# HX711_1.net
KiCad netlist of a schematic drawn in Altium Designer
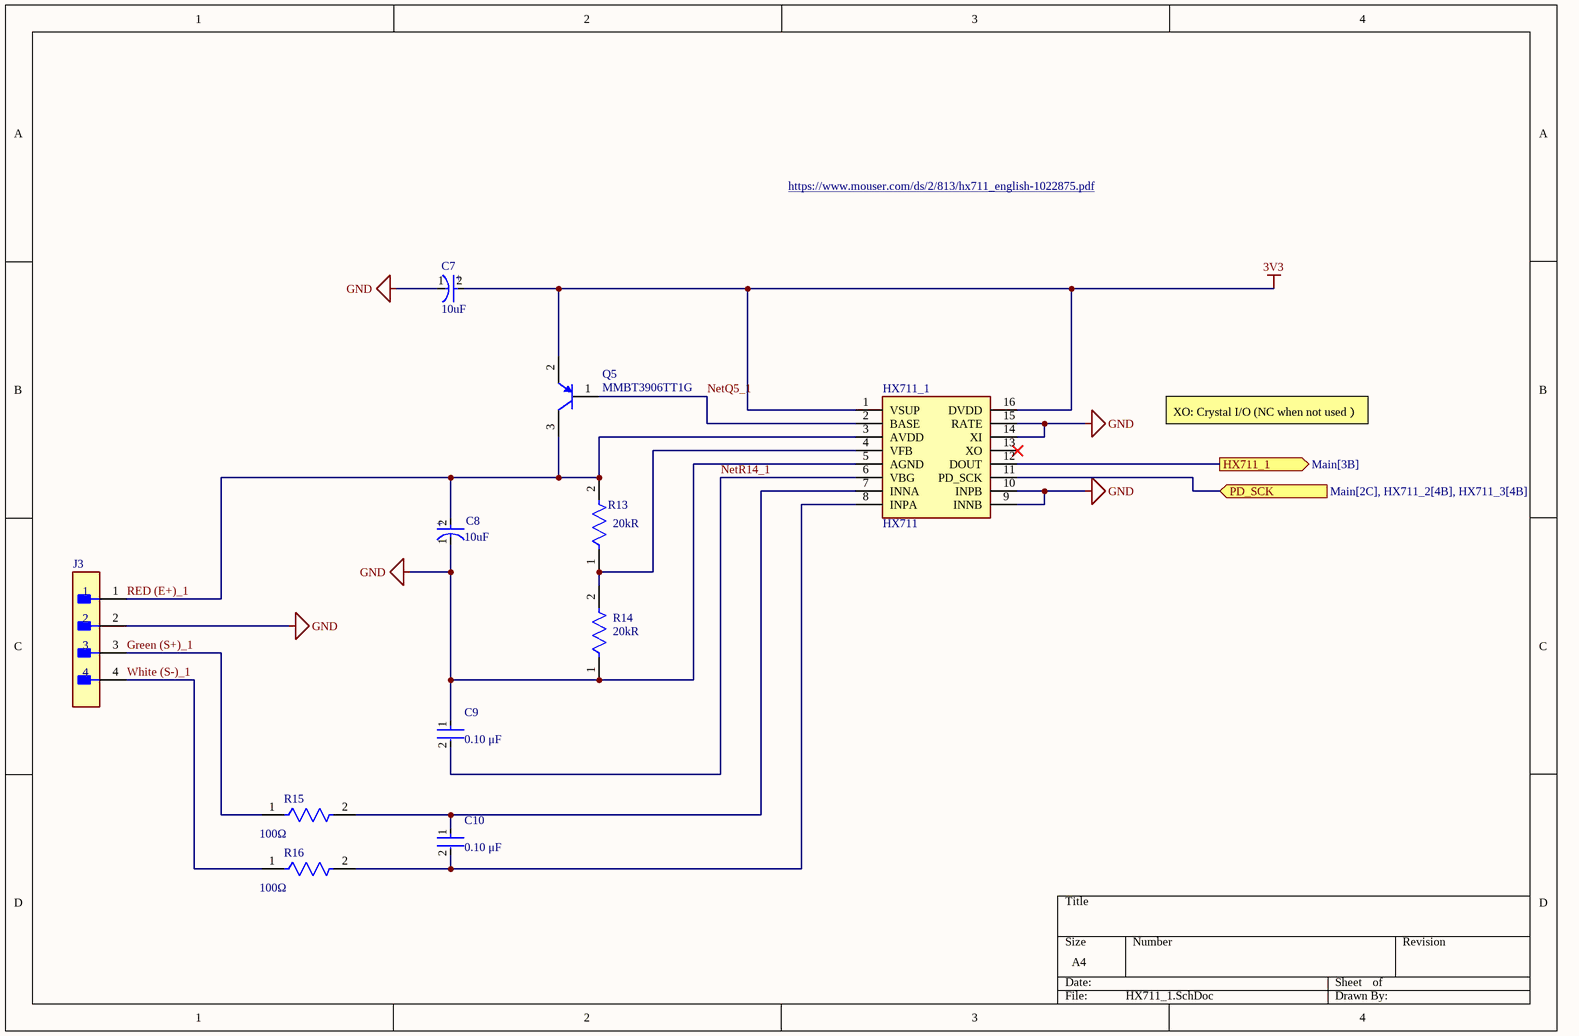
[diagram p0: HX711_1.SchDoc]

(export (version "E")
  (design (tool "Eeschema 10.0.6"))
  (components
    (comp (ref "C7")
      (value "EDK106M035A9BAA")
      (footprint "FP-EDK9B-MFG")
      (description "CAP ALUM 10UF 20% 35V SMD")
      (fields
        (field (name "CAPACITANCE") "10uF")
        (field (name "MANUFACTURER") "Kemet")
        (field (name "OCTOPART") "https://octopart.com/edk106m035a9baa-kemet-26722193")
      )
      (libsource (lib "Altium Content Vault") (part "cf48714ba7e38822c1575c7ec0b6d1f"))
    )
    (comp (ref "C8")
      (value "EDK106M035A9BAA")
      (footprint "FP-EDK9B-MFG")
      (description "CAP ALUM 10UF 20% 35V SMD")
      (fields
        (field (name "CAPACITANCE") "10uF")
        (field (name "MANUFACTURER") "Kemet")
        (field (name "OCTOPART") "https://octopart.com/edk106m035a9baa-kemet-26722193")
      )
      (libsource (lib "Altium Content Vault") (part "cf48714ba7e38822c1575c7ec0b6d1f"))
    )
    (comp (ref "C9")
      (value "0.10 μF")
      (footprint "FP-C0603C-CF-MFG")
      (description "CAP CER 0.1UF 25V X7R 0603")
      (fields
        (field (name "OCTOPART") "https://octopart.com/c0603c104k3rac7411-kemet-9138804")
        (field (name "MANUFACTURER") "KEMET")
      )
      (libsource (lib "Altium Content Vault") (part "b4654b650e69147ec39a6b967a45e02"))
    )
    (comp (ref "C10")
      (value "0.10 μF")
      (footprint "FP-C0603C-CF-MFG")
      (description "CAP CER 0.1UF 25V X7R 0603")
      (fields
        (field (name "OCTOPART") "https://octopart.com/c0603c104k3rac7411-kemet-9138804")
        (field (name "MANUFACTURER") "KEMET")
      )
      (libsource (lib "Altium Content Vault") (part "b4654b650e69147ec39a6b967a45e02"))
    )
    (comp (ref "HX711_1")
      (value "HX711")
      (footprint "SamacSys:SOIC127P600X160-16N")
      (description "Integrated Circuit")
      (libsource (lib "*") (part "HX711"))
    )
    (comp (ref "J3")
      (value "TSW-104-23-T-S")
      (footprint "FP-TSW-104-23-T-S-MFG")
      (description "CONN HEADER VERT 4POS 2.54MM")
      (libsource (lib "Altium Content Vault") (part "f33e0d423099bbb9e64512431cdbdf7"))
    )
    (comp (ref "Q5")
      (value "MMBT3906TT1G")
      (footprint "ONSC-SC-75-3-463-01_V")
      (description "General Purpose Transistor, PNP Silicon, 3-Pin SC-75, Pb-Free, Tape and Reel")
      (fields (field (name "MANUFACTURER") "On Semiconductor"))
      (libsource (lib "Altium Content Vault") (part "ONSC-PNP-B1E2C3-3"))
    )
    (comp (ref "R13")
      (value "CRCW060320K0FKEAHP")
      (footprint "FP-CRCW0603-HPe3-MFG")
      (description "RES Thick Film, 20kΩ, 1%, 0.33W, 100ppm/°C, 0603")
      (fields (field (name "RESISTANCE") "20kR") (field (name "TOLERANCE") "1%"))
      (libsource (lib "Altium Content Vault") (part "1029c3af85768c4190bb7ad29bc67b5"))
    )
    (comp (ref "R14")
      (value "CRCW060320K0FKEAHP")
      (footprint "FP-CRCW0603-HPe3-MFG")
      (description "RES Thick Film, 20kΩ, 1%, 0.33W, 100ppm/°C, 0603")
      (fields (field (name "RESISTANCE") "20kR") (field (name "TOLERANCE") "1%"))
      (libsource (lib "Altium Content Vault") (part "1029c3af85768c4190bb7ad29bc67b5"))
    )
    (comp (ref "R15")
      (value "100Ω")
      (footprint "FP-RT0603-MFG")
      (description "RES SMD 100 OHM 1% 1/10W 0603")
      (fields
        (field (name "MANUFACTURER PART NUMBER") "RT0603FRE07100RL")
        (field (name "MANUFACTURER") "Yageo")
      )
      (libsource (lib "Altium Content Vault") (part "1029c3af85768c4190bb7ad29bc67b5"))
    )
    (comp (ref "R16")
      (value "100Ω")
      (footprint "FP-RT0603-MFG")
      (description "RES SMD 100 OHM 1% 1/10W 0603")
      (fields
        (field (name "MANUFACTURER PART NUMBER") "RT0603FRE07100RL")
        (field (name "MANUFACTURER") "Yageo")
      )
      (libsource (lib "Altium Content Vault") (part "1029c3af85768c4190bb7ad29bc67b5"))
    )
  )
  (nets
    (net (code "1") (name "/Green (S+)_1") (class "Default")
      (node (ref "J3") (pin "3") (pinfunction "3_3") (pintype "passive"))
      (node (ref "R15") (pin "1") (pinfunction "1_1") (pintype "passive"))
    )
    (net (code "2") (name "/HX711_1") (class "Default")
      (node (ref "HX711_1") (pin "12") (pinfunction "DOUT_12") (pintype "passive"))
    )
    (net (code "3") (name "/NetQ5_1") (class "Default")
      (node (ref "HX711_1") (pin "2") (pinfunction "BASE_2") (pintype "passive"))
      (node (ref "Q5") (pin "1") (pinfunction "B_1") (pintype "passive"))
    )
    (net (code "4") (name "/NetR14_1") (class "Default")
      (node (ref "C9") (pin "2") (pinfunction "2_2") (pintype "passive"))
      (node (ref "HX711_1") (pin "6") (pinfunction "VBG_6") (pintype "passive"))
    )
    (net (code "5") (name "/PD_SCK") (class "Default")
      (node (ref "HX711_1") (pin "11") (pinfunction "PD_SCK_11") (pintype "passive"))
    )
    (net (code "6") (name "/RED (E+)_1") (class "Default")
      (node (ref "C8") (pin "2") (pinfunction "A_2") (pintype "passive"))
      (node (ref "HX711_1") (pin "3") (pinfunction "AVDD_3") (pintype "passive"))
      (node (ref "J3") (pin "1") (pinfunction "1_1") (pintype "passive"))
      (node (ref "Q5") (pin "3") (pinfunction "C_3") (pintype "passive"))
      (node (ref "R13") (pin "2") (pinfunction "2_2") (pintype "passive"))
    )
    (net (code "7") (name "/White (S-)_1") (class "Default")
      (node (ref "J3") (pin "4") (pinfunction "4_4") (pintype "passive"))
      (node (ref "R16") (pin "1") (pinfunction "1_1") (pintype "passive"))
    )
    (net (code "8") (name "3V3") (class "Default")
      (node (ref "C7") (pin "2") (pinfunction "A_2") (pintype "passive"))
      (node (ref "HX711_1") (pin "1") (pinfunction "VSUP_1") (pintype "passive"))
      (node (ref "HX711_1") (pin "16") (pinfunction "DVDD_16") (pintype "passive"))
      (node (ref "Q5") (pin "2") (pinfunction "E_2") (pintype "passive"))
    )
    (net (code "9") (name "GND") (class "Default")
      (node (ref "C7") (pin "1") (pinfunction "C_1") (pintype "passive"))
      (node (ref "C8") (pin "1") (pinfunction "C_1") (pintype "passive"))
      (node (ref "C9") (pin "1") (pinfunction "1_1") (pintype "passive"))
      (node (ref "HX711_1") (pin "10") (pinfunction "INPB_10") (pintype "passive"))
      (node (ref "HX711_1") (pin "14") (pinfunction "XI_14") (pintype "passive"))
      (node (ref "HX711_1") (pin "15") (pinfunction "RATE_15") (pintype "passive"))
      (node (ref "HX711_1") (pin "5") (pinfunction "AGND_5") (pintype "passive"))
      (node (ref "HX711_1") (pin "9") (pinfunction "INNB_9") (pintype "passive"))
      (node (ref "J3") (pin "2") (pinfunction "2_2") (pintype "passive"))
      (node (ref "R14") (pin "1") (pinfunction "1_1") (pintype "passive"))
    )
    (net (code "10") (name "Net-(HX711_1-INNA)") (class "Default")
      (node (ref "C10") (pin "1") (pinfunction "1_1") (pintype "passive"))
      (node (ref "HX711_1") (pin "7") (pinfunction "INNA_7") (pintype "passive"))
      (node (ref "R15") (pin "2") (pinfunction "2_2") (pintype "passive"))
    )
    (net (code "11") (name "Net-(HX711_1-INPA)") (class "Default")
      (node (ref "C10") (pin "2") (pinfunction "2_2") (pintype "passive"))
      (node (ref "HX711_1") (pin "8") (pinfunction "INPA_8") (pintype "passive"))
      (node (ref "R16") (pin "2") (pinfunction "2_2") (pintype "passive"))
    )
    (net (code "12") (name "Net-(HX711_1-VFB)") (class "Default")
      (node (ref "HX711_1") (pin "4") (pinfunction "VFB_4") (pintype "passive"))
      (node (ref "R13") (pin "1") (pinfunction "1_1") (pintype "passive"))
      (node (ref "R14") (pin "2") (pinfunction "2_2") (pintype "passive"))
    )
    (net (code "13") (name "unconnected-(HX711_1-XO-Pad13)") (class "Default")
      (node (ref "HX711_1") (pin "13") (pinfunction "XO_13") (pintype "passive+no_connect"))
    )
  )
)
